# Preamp_board2.net
KiCad netlist of a schematic drawn in EAGLE
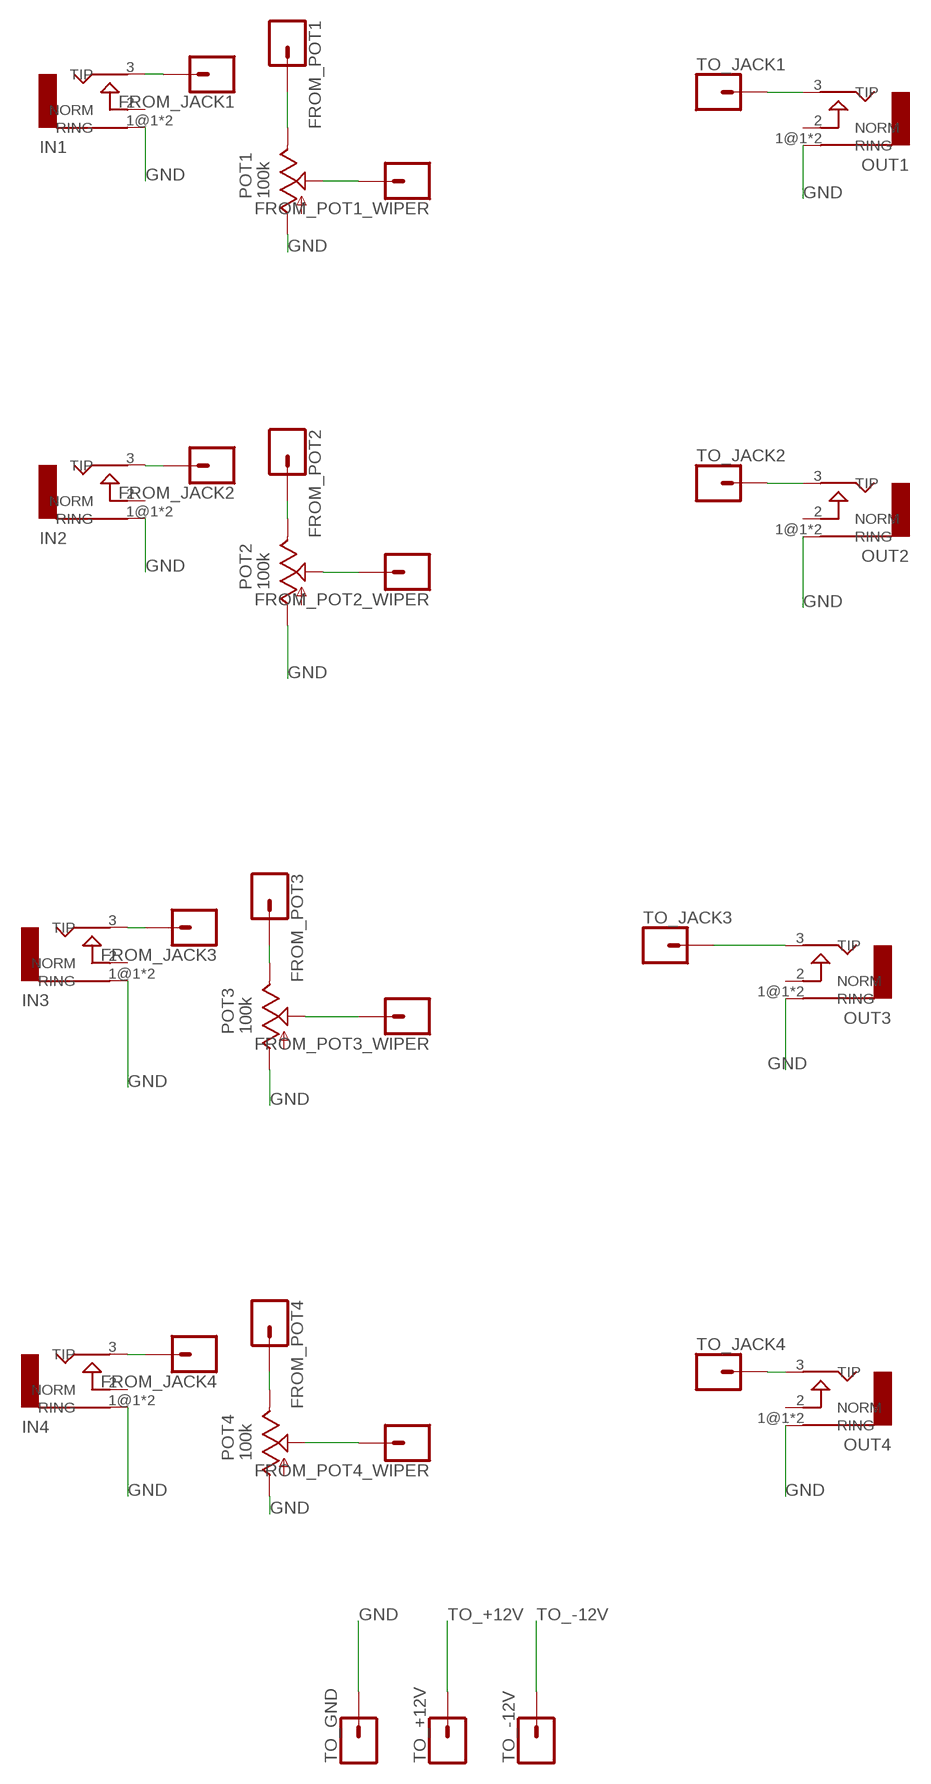
[diagram p0: schematic, sheet 1]

(export (version "E")
  (design (tool "Eeschema 10.0.6"))
  (components
    (comp (ref "FROM_JACK1")
      (value "CONN_01PTH_LONGPAD")
      (footprint "eagle-import:1X01_LONGPAD")
      (libsource (lib "eagle-import") (part "CONN_01PTH_LONGPAD"))
    )
    (comp (ref "FROM_JACK2")
      (value "CONN_01PTH_LONGPAD")
      (footprint "eagle-import:1X01_LONGPAD")
      (libsource (lib "eagle-import") (part "CONN_01PTH_LONGPAD"))
    )
    (comp (ref "FROM_JACK3")
      (value "CONN_01PTH_LONGPAD")
      (footprint "eagle-import:1X01_LONGPAD")
      (libsource (lib "eagle-import") (part "CONN_01PTH_LONGPAD"))
    )
    (comp (ref "FROM_JACK4")
      (value "CONN_01PTH_LONGPAD")
      (footprint "eagle-import:1X01_LONGPAD")
      (libsource (lib "eagle-import") (part "CONN_01PTH_LONGPAD"))
    )
    (comp (ref "FROM_POT1")
      (value "CONN_01PTH_LONGPAD")
      (footprint "eagle-import:1X01_LONGPAD")
      (libsource (lib "eagle-import") (part "CONN_01PTH_LONGPAD"))
    )
    (comp (ref "FROM_POT1_WIPER")
      (value "CONN_01PTH_LONGPAD")
      (footprint "eagle-import:1X01_LONGPAD")
      (libsource (lib "eagle-import") (part "CONN_01PTH_LONGPAD"))
    )
    (comp (ref "FROM_POT2")
      (value "CONN_01PTH_LONGPAD")
      (footprint "eagle-import:1X01_LONGPAD")
      (libsource (lib "eagle-import") (part "CONN_01PTH_LONGPAD"))
    )
    (comp (ref "FROM_POT2_WIPER")
      (value "CONN_01PTH_LONGPAD")
      (footprint "eagle-import:1X01_LONGPAD")
      (libsource (lib "eagle-import") (part "CONN_01PTH_LONGPAD"))
    )
    (comp (ref "FROM_POT3")
      (value "CONN_01PTH_LONGPAD")
      (footprint "eagle-import:1X01_LONGPAD")
      (libsource (lib "eagle-import") (part "CONN_01PTH_LONGPAD"))
    )
    (comp (ref "FROM_POT3_WIPER")
      (value "CONN_01PTH_LONGPAD")
      (footprint "eagle-import:1X01_LONGPAD")
      (libsource (lib "eagle-import") (part "CONN_01PTH_LONGPAD"))
    )
    (comp (ref "FROM_POT4")
      (value "CONN_01PTH_LONGPAD")
      (footprint "eagle-import:1X01_LONGPAD")
      (libsource (lib "eagle-import") (part "CONN_01PTH_LONGPAD"))
    )
    (comp (ref "FROM_POT4_WIPER")
      (value "CONN_01PTH_LONGPAD")
      (footprint "eagle-import:1X01_LONGPAD")
      (libsource (lib "eagle-import") (part "CONN_01PTH_LONGPAD"))
    )
    (comp (ref "IN1")
      (value "AUDIO-JACKERTHENVAR")
      (footprint "eagle-import:ERTHENVAR-JACK")
      (libsource (lib "eagle-import") (part "AUDIO-JACKERTHENVAR"))
    )
    (comp (ref "IN2")
      (value "AUDIO-JACKERTHENVAR")
      (footprint "eagle-import:ERTHENVAR-JACK")
      (libsource (lib "eagle-import") (part "AUDIO-JACKERTHENVAR"))
    )
    (comp (ref "IN3")
      (value "AUDIO-JACKERTHENVAR")
      (footprint "eagle-import:ERTHENVAR-JACK")
      (libsource (lib "eagle-import") (part "AUDIO-JACKERTHENVAR"))
    )
    (comp (ref "IN4")
      (value "AUDIO-JACKERTHENVAR")
      (footprint "eagle-import:ERTHENVAR-JACK")
      (libsource (lib "eagle-import") (part "AUDIO-JACKERTHENVAR"))
    )
    (comp (ref "OUT1")
      (value "AUDIO-JACKERTHENVAR")
      (footprint "eagle-import:ERTHENVAR-JACK")
      (libsource (lib "eagle-import") (part "AUDIO-JACKERTHENVAR"))
    )
    (comp (ref "OUT2")
      (value "AUDIO-JACKERTHENVAR")
      (footprint "eagle-import:ERTHENVAR-JACK")
      (libsource (lib "eagle-import") (part "AUDIO-JACKERTHENVAR"))
    )
    (comp (ref "OUT3")
      (value "AUDIO-JACKERTHENVAR")
      (footprint "eagle-import:ERTHENVAR-JACK")
      (libsource (lib "eagle-import") (part "AUDIO-JACKERTHENVAR"))
    )
    (comp (ref "OUT4")
      (value "AUDIO-JACKERTHENVAR")
      (footprint "eagle-import:ERTHENVAR-JACK")
      (libsource (lib "eagle-import") (part "AUDIO-JACKERTHENVAR"))
    )
    (comp (ref "POT1")
      (value "100k")
      (footprint "eagle-import:9MM_SNAP-IN_POT")
      (libsource (lib "eagle-import") (part "9MM_SNAP-IN_POT_"))
    )
    (comp (ref "POT2")
      (value "100k")
      (footprint "eagle-import:9MM_SNAP-IN_POT")
      (libsource (lib "eagle-import") (part "9MM_SNAP-IN_POT_"))
    )
    (comp (ref "POT3")
      (value "100k")
      (footprint "eagle-import:9MM_SNAP-IN_POT")
      (libsource (lib "eagle-import") (part "9MM_SNAP-IN_POT_"))
    )
    (comp (ref "POT4")
      (value "100k")
      (footprint "eagle-import:9MM_SNAP-IN_POT")
      (libsource (lib "eagle-import") (part "9MM_SNAP-IN_POT_"))
    )
    (comp (ref "TO_+12V")
      (value "CONN_01PTH_LONGPAD")
      (footprint "eagle-import:1X01_LONGPAD")
      (libsource (lib "eagle-import") (part "CONN_01PTH_LONGPAD"))
    )
    (comp (ref "TO_-12V")
      (value "CONN_01PTH_LONGPAD")
      (footprint "eagle-import:1X01_LONGPAD")
      (libsource (lib "eagle-import") (part "CONN_01PTH_LONGPAD"))
    )
    (comp (ref "TO_GND")
      (value "CONN_01PTH_LONGPAD")
      (footprint "eagle-import:1X01_LONGPAD")
      (libsource (lib "eagle-import") (part "CONN_01PTH_LONGPAD"))
    )
    (comp (ref "TO_JACK1")
      (value "CONN_01PTH_LONGPAD")
      (footprint "eagle-import:1X01_LONGPAD")
      (libsource (lib "eagle-import") (part "CONN_01PTH_LONGPAD"))
    )
    (comp (ref "TO_JACK2")
      (value "CONN_01PTH_LONGPAD")
      (footprint "eagle-import:1X01_LONGPAD")
      (libsource (lib "eagle-import") (part "CONN_01PTH_LONGPAD"))
    )
    (comp (ref "TO_JACK3")
      (value "CONN_01PTH_LONGPAD")
      (footprint "eagle-import:1X01_LONGPAD")
      (libsource (lib "eagle-import") (part "CONN_01PTH_LONGPAD"))
    )
    (comp (ref "TO_JACK4")
      (value "CONN_01PTH_LONGPAD")
      (footprint "eagle-import:1X01_LONGPAD")
      (libsource (lib "eagle-import") (part "CONN_01PTH_LONGPAD"))
    )
  )
  (nets
    (net (code "1") (name "/GND") (class "Default")
      (node (ref "IN1") (pin "1@1") (pinfunction "RING_1@1") (pintype "bidirectional"))
      (node (ref "IN1") (pin "1@2") (pinfunction "RING_1@2") (pintype "bidirectional"))
      (node (ref "IN2") (pin "1@1") (pinfunction "RING_1@1") (pintype "bidirectional"))
      (node (ref "IN2") (pin "1@2") (pinfunction "RING_1@2") (pintype "bidirectional"))
      (node (ref "IN3") (pin "1@1") (pinfunction "RING_1@1") (pintype "bidirectional"))
      (node (ref "IN3") (pin "1@2") (pinfunction "RING_1@2") (pintype "bidirectional"))
      (node (ref "IN4") (pin "1@1") (pinfunction "RING_1@1") (pintype "bidirectional"))
      (node (ref "IN4") (pin "1@2") (pinfunction "RING_1@2") (pintype "bidirectional"))
      (node (ref "OUT1") (pin "1@1") (pinfunction "RING_1@1") (pintype "bidirectional"))
      (node (ref "OUT1") (pin "1@2") (pinfunction "RING_1@2") (pintype "bidirectional"))
      (node (ref "OUT2") (pin "1@1") (pinfunction "RING_1@1") (pintype "bidirectional"))
      (node (ref "OUT2") (pin "1@2") (pinfunction "RING_1@2") (pintype "bidirectional"))
      (node (ref "OUT3") (pin "1@1") (pinfunction "RING_1@1") (pintype "bidirectional"))
      (node (ref "OUT3") (pin "1@2") (pinfunction "RING_1@2") (pintype "bidirectional"))
      (node (ref "OUT4") (pin "1@1") (pinfunction "RING_1@1") (pintype "bidirectional"))
      (node (ref "OUT4") (pin "1@2") (pinfunction "RING_1@2") (pintype "bidirectional"))
      (node (ref "POT1") (pin "1") (pinfunction "A_1") (pintype "passive"))
      (node (ref "POT2") (pin "1") (pinfunction "A_1") (pintype "passive"))
      (node (ref "POT3") (pin "1") (pinfunction "A_1") (pintype "passive"))
      (node (ref "POT4") (pin "1") (pinfunction "A_1") (pintype "passive"))
      (node (ref "TO_GND") (pin "1") (pinfunction "1_1") (pintype "passive"))
    )
    (net (code "2") (name "/TO_+12V") (class "Default")
      (node (ref "TO_+12V") (pin "1") (pinfunction "1_1") (pintype "passive"))
    )
    (net (code "3") (name "/TO_-12V") (class "Default")
      (node (ref "TO_-12V") (pin "1") (pinfunction "1_1") (pintype "passive"))
    )
    (net (code "4") (name "Net-(IN1-TIP)") (class "Default")
      (node (ref "FROM_JACK1") (pin "1") (pinfunction "1_1") (pintype "passive"))
      (node (ref "IN1") (pin "3") (pinfunction "TIP_3") (pintype "bidirectional"))
    )
    (net (code "5") (name "Net-(IN2-TIP)") (class "Default")
      (node (ref "FROM_JACK2") (pin "1") (pinfunction "1_1") (pintype "passive"))
      (node (ref "IN2") (pin "3") (pinfunction "TIP_3") (pintype "bidirectional"))
    )
    (net (code "6") (name "Net-(IN3-TIP)") (class "Default")
      (node (ref "FROM_JACK3") (pin "1") (pinfunction "1_1") (pintype "passive"))
      (node (ref "IN3") (pin "3") (pinfunction "TIP_3") (pintype "bidirectional"))
    )
    (net (code "7") (name "Net-(IN4-TIP)") (class "Default")
      (node (ref "FROM_JACK4") (pin "1") (pinfunction "1_1") (pintype "passive"))
      (node (ref "IN4") (pin "3") (pinfunction "TIP_3") (pintype "bidirectional"))
    )
    (net (code "8") (name "Net-(OUT1-TIP)") (class "Default")
      (node (ref "OUT1") (pin "3") (pinfunction "TIP_3") (pintype "bidirectional"))
      (node (ref "TO_JACK1") (pin "1") (pinfunction "1_1") (pintype "passive"))
    )
    (net (code "9") (name "Net-(OUT2-TIP)") (class "Default")
      (node (ref "OUT2") (pin "3") (pinfunction "TIP_3") (pintype "bidirectional"))
      (node (ref "TO_JACK2") (pin "1") (pinfunction "1_1") (pintype "passive"))
    )
    (net (code "10") (name "Net-(OUT3-TIP)") (class "Default")
      (node (ref "OUT3") (pin "3") (pinfunction "TIP_3") (pintype "bidirectional"))
      (node (ref "TO_JACK3") (pin "1") (pinfunction "1_1") (pintype "passive"))
    )
    (net (code "11") (name "Net-(OUT4-TIP)") (class "Default")
      (node (ref "OUT4") (pin "3") (pinfunction "TIP_3") (pintype "bidirectional"))
      (node (ref "TO_JACK4") (pin "1") (pinfunction "1_1") (pintype "passive"))
    )
    (net (code "12") (name "Net-(POT1-E)") (class "Default")
      (node (ref "FROM_POT1") (pin "1") (pinfunction "1_1") (pintype "passive"))
      (node (ref "POT1") (pin "3") (pinfunction "E_3") (pintype "passive"))
    )
    (net (code "13") (name "Net-(POT1-S)") (class "Default")
      (node (ref "FROM_POT1_WIPER") (pin "1") (pinfunction "1_1") (pintype "passive"))
      (node (ref "POT1") (pin "2") (pinfunction "S_2") (pintype "passive"))
    )
    (net (code "14") (name "Net-(POT2-E)") (class "Default")
      (node (ref "FROM_POT2") (pin "1") (pinfunction "1_1") (pintype "passive"))
      (node (ref "POT2") (pin "3") (pinfunction "E_3") (pintype "passive"))
    )
    (net (code "15") (name "Net-(POT2-S)") (class "Default")
      (node (ref "FROM_POT2_WIPER") (pin "1") (pinfunction "1_1") (pintype "passive"))
      (node (ref "POT2") (pin "2") (pinfunction "S_2") (pintype "passive"))
    )
    (net (code "16") (name "Net-(POT3-E)") (class "Default")
      (node (ref "FROM_POT3") (pin "1") (pinfunction "1_1") (pintype "passive"))
      (node (ref "POT3") (pin "3") (pinfunction "E_3") (pintype "passive"))
    )
    (net (code "17") (name "Net-(POT3-S)") (class "Default")
      (node (ref "FROM_POT3_WIPER") (pin "1") (pinfunction "1_1") (pintype "passive"))
      (node (ref "POT3") (pin "2") (pinfunction "S_2") (pintype "passive"))
    )
    (net (code "18") (name "Net-(POT4-E)") (class "Default")
      (node (ref "FROM_POT4") (pin "1") (pinfunction "1_1") (pintype "passive"))
      (node (ref "POT4") (pin "3") (pinfunction "E_3") (pintype "passive"))
    )
    (net (code "19") (name "Net-(POT4-S)") (class "Default")
      (node (ref "FROM_POT4_WIPER") (pin "1") (pinfunction "1_1") (pintype "passive"))
      (node (ref "POT4") (pin "2") (pinfunction "S_2") (pintype "passive"))
    )
    (net (code "20") (name "unconnected-(IN1-NORM-Pad2)") (class "Default")
      (node (ref "IN1") (pin "2") (pinfunction "NORM_2") (pintype "bidirectional"))
    )
    (net (code "21") (name "unconnected-(IN2-NORM-Pad2)") (class "Default")
      (node (ref "IN2") (pin "2") (pinfunction "NORM_2") (pintype "bidirectional"))
    )
    (net (code "22") (name "unconnected-(IN3-NORM-Pad2)") (class "Default")
      (node (ref "IN3") (pin "2") (pinfunction "NORM_2") (pintype "bidirectional"))
    )
    (net (code "23") (name "unconnected-(IN4-NORM-Pad2)") (class "Default")
      (node (ref "IN4") (pin "2") (pinfunction "NORM_2") (pintype "bidirectional"))
    )
    (net (code "24") (name "unconnected-(OUT1-NORM-Pad2)") (class "Default")
      (node (ref "OUT1") (pin "2") (pinfunction "NORM_2") (pintype "bidirectional"))
    )
    (net (code "25") (name "unconnected-(OUT2-NORM-Pad2)") (class "Default")
      (node (ref "OUT2") (pin "2") (pinfunction "NORM_2") (pintype "bidirectional"))
    )
    (net (code "26") (name "unconnected-(OUT3-NORM-Pad2)") (class "Default")
      (node (ref "OUT3") (pin "2") (pinfunction "NORM_2") (pintype "bidirectional"))
    )
    (net (code "27") (name "unconnected-(OUT4-NORM-Pad2)") (class "Default")
      (node (ref "OUT4") (pin "2") (pinfunction "NORM_2") (pintype "bidirectional"))
    )
  )
)
